# Master_Device.net
KiCad netlist of a schematic drawn in EAGLE
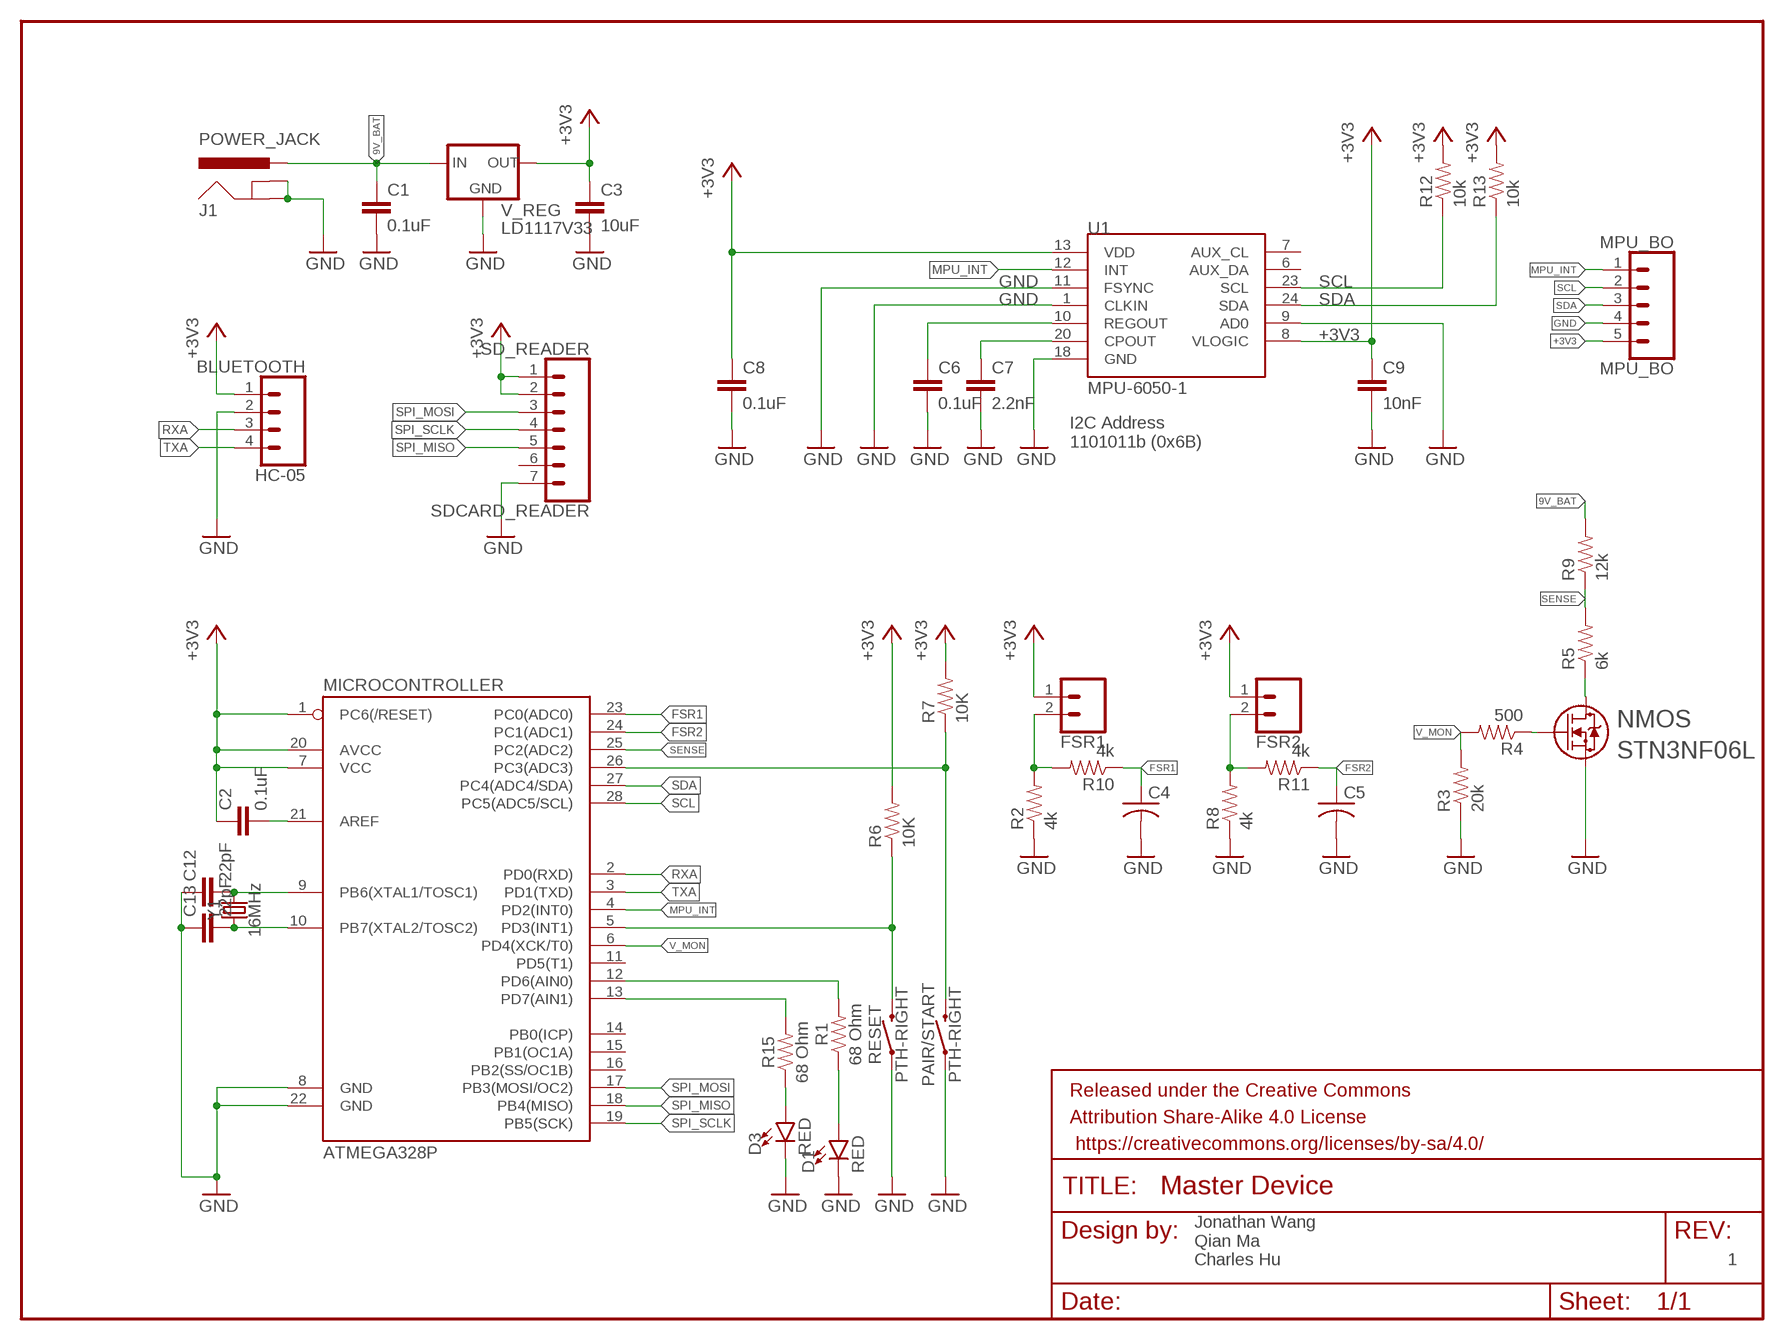
[diagram p0: schematic, sheet 1]

(export (version "E")
  (design (tool "Eeschema 10.0.6"))
  (components
    (comp (ref "C1")
      (value "0.1uF")
      (footprint "eagle-import:0603-CAP")
      (libsource (lib "eagle-import") (part "CAP0603-CAP"))
    )
    (comp (ref "C2")
      (value "0.1uF")
      (footprint "eagle-import:0603-CAP")
      (libsource (lib "eagle-import") (part "CAP0603-CAP"))
    )
    (comp (ref "C3")
      (value "10uF")
      (footprint "eagle-import:0603-CAP")
      (libsource (lib "eagle-import") (part "CAP0603-CAP"))
    )
    (comp (ref "C4")
      (value "C-US050-050X075")
      (footprint "eagle-import:C050-050X075")
      (libsource (lib "eagle-import") (part "C-US050-050X075"))
    )
    (comp (ref "C5")
      (value "C-US050-050X075")
      (footprint "eagle-import:C050-050X075")
      (libsource (lib "eagle-import") (part "C-US050-050X075"))
    )
    (comp (ref "C6")
      (value "0.1uF")
      (footprint "eagle-import:0603-CAP")
      (libsource (lib "eagle-import") (part "CAP0603-CAP"))
    )
    (comp (ref "C7")
      (value "2.2nF")
      (footprint "eagle-import:0603-CAP")
      (libsource (lib "eagle-import") (part "CAP0603-CAP"))
    )
    (comp (ref "C8")
      (value "0.1uF")
      (footprint "eagle-import:0603-CAP")
      (libsource (lib "eagle-import") (part "CAP0603-CAP"))
    )
    (comp (ref "C9")
      (value "10nF")
      (footprint "eagle-import:0603-CAP")
      (libsource (lib "eagle-import") (part "CAP0603-CAP"))
    )
    (comp (ref "C12")
      (value "22pF")
      (footprint "eagle-import:0603")
      (libsource (lib "eagle-import") (part "22PF-0603-50V-5%"))
    )
    (comp (ref "C13")
      (value "22pF")
      (footprint "eagle-import:0603")
      (libsource (lib "eagle-import") (part "22PF-0603-50V-5%"))
    )
    (comp (ref "D1")
      (value "RED")
      (footprint "eagle-import:LED_3MM")
      (libsource (lib "eagle-import") (part "LED3MM"))
    )
    (comp (ref "D3")
      (value "RED")
      (footprint "eagle-import:LED_3MM")
      (libsource (lib "eagle-import") (part "LED3MM"))
    )
    (comp (ref "FRAME1")
      (value "FRAME-LETTERNO_PACKAGE")
      (footprint "eagle-import:DUMMY")
      (fields (field (name "DESIGNER") "Nobody"))
      (libsource (lib "eagle-import") (part "FRAME-LETTERNO_PACKAGE"))
    )
    (comp (ref "FSR1")
      (value "CONN_02")
      (footprint "eagle-import:1X02")
      (libsource (lib "eagle-import") (part "CONN_02"))
    )
    (comp (ref "FSR2")
      (value "CONN_02")
      (footprint "eagle-import:1X02")
      (libsource (lib "eagle-import") (part "CONN_02"))
    )
    (comp (ref "HC-05")
      (value "BLUETOOTH")
      (footprint "eagle-import:1X04")
      (libsource (lib "eagle-import") (part "CONN_04"))
    )
    (comp (ref "J1")
      (value "POWER_JACK")
      (footprint "eagle-import:POWER_JACK_PTH")
      (libsource (lib "eagle-import") (part "POWER_JACK"))
    )
    (comp (ref "MICROCONTROLLER")
      (value "ATMEGA328P")
      (footprint "eagle-import:DIP28")
      (libsource (lib "eagle-import") (part "ATMEGA328P_PDIP"))
    )
    (comp (ref "MPU_BO")
      (value "MPU_BO")
      (footprint "eagle-import:1X05")
      (libsource (lib "eagle-import") (part "CONN_05"))
    )
    (comp (ref "NMOS")
      (value "STN3NF06L")
      (footprint "eagle-import:SOT-223")
      (libsource (lib "eagle-import") (part "STN3NF06L"))
    )
    (comp (ref "PAIR/START")
      (value "PTH-RIGHT")
      (footprint "eagle-import:TACTILE_SWITCH_PTH_RIGHT_ANGLE_KIT")
      (libsource (lib "eagle-import") (part "MOMENTARY-SWITCH-SPST-PTH-RIGHT-ANGLE-KIT"))
    )
    (comp (ref "R1")
      (value "68 Ohm")
      (footprint "eagle-import:0603")
      (libsource (lib "eagle-import") (part "68OHM-0603-1/10W-1%"))
    )
    (comp (ref "R2")
      (value "4k")
      (footprint "eagle-import:0603-RES")
      (libsource (lib "eagle-import") (part "10KOHM-1/10W-1%(0603)0603"))
    )
    (comp (ref "R3")
      (value "20k")
      (footprint "eagle-import:0603-RES")
      (libsource (lib "eagle-import") (part "10KOHM-1/10W-1%(0603)0603"))
    )
    (comp (ref "R4")
      (value "500")
      (footprint "eagle-import:0603-RES")
      (libsource (lib "eagle-import") (part "10KOHM-1/10W-1%(0603)0603"))
    )
    (comp (ref "R5")
      (value "6k")
      (footprint "eagle-import:0603-RES")
      (libsource (lib "eagle-import") (part "10KOHM-1/10W-1%(0603)0603"))
    )
    (comp (ref "R6")
      (value "10K")
      (footprint "eagle-import:0603-RES")
      (libsource (lib "eagle-import") (part "10KOHM-1/10W-1%(0603)0603"))
    )
    (comp (ref "R7")
      (value "10K")
      (footprint "eagle-import:0603-RES")
      (libsource (lib "eagle-import") (part "10KOHM-1/10W-1%(0603)0603"))
    )
    (comp (ref "R8")
      (value "4k")
      (footprint "eagle-import:0603-RES")
      (libsource (lib "eagle-import") (part "10KOHM-1/10W-1%(0603)0603"))
    )
    (comp (ref "R9")
      (value "12k")
      (footprint "eagle-import:0603-RES")
      (libsource (lib "eagle-import") (part "10KOHM-1/10W-1%(0603)0603"))
    )
    (comp (ref "R10")
      (value "4k")
      (footprint "eagle-import:0603-RES")
      (libsource (lib "eagle-import") (part "10KOHM-1/10W-1%(0603)0603"))
    )
    (comp (ref "R11")
      (value "4k")
      (footprint "eagle-import:0603-RES")
      (libsource (lib "eagle-import") (part "10KOHM-1/10W-1%(0603)0603"))
    )
    (comp (ref "R12")
      (value "10k")
      (footprint "eagle-import:0603-RES")
      (libsource (lib "eagle-import") (part "RESISTOR0603-RES"))
    )
    (comp (ref "R13")
      (value "10k")
      (footprint "eagle-import:0603-RES")
      (libsource (lib "eagle-import") (part "RESISTOR0603-RES"))
    )
    (comp (ref "R15")
      (value "68 Ohm")
      (footprint "eagle-import:0603")
      (libsource (lib "eagle-import") (part "68OHM-0603-1/10W-1%"))
    )
    (comp (ref "RESET")
      (value "PTH-RIGHT")
      (footprint "eagle-import:TACTILE_SWITCH_PTH_RIGHT_ANGLE_KIT")
      (libsource (lib "eagle-import") (part "MOMENTARY-SWITCH-SPST-PTH-RIGHT-ANGLE-KIT"))
    )
    (comp (ref "SDCARD_READER")
      (value "SD_READER")
      (footprint "eagle-import:1X07")
      (libsource (lib "eagle-import") (part "CONN_07"))
    )
    (comp (ref "U1")
      (value "MPU-6050-1")
      (footprint "eagle-import:QFN-24-4MM2")
      (libsource (lib "eagle-import") (part "MPU-6050-1"))
    )
    (comp (ref "V_REG")
      (value "LD1117V33")
      (footprint "eagle-import:78XXL")
      (libsource (lib "eagle-import") (part "V_REG_LD1117VXX"))
    )
    (comp (ref "Y1")
      (value "16MHz")
      (footprint "eagle-import:HC49US")
      (libsource (lib "eagle-import") (part "CRYSTAL-16MHZPTH-HC49US"))
    )
  )
  (nets
    (net (code "1") (name "+3V3") (class "Default")
      (node (ref "C2") (pin "1") (pinfunction "1_1") (pintype "passive"))
      (node (ref "C3") (pin "1") (pinfunction "1_1") (pintype "passive"))
      (node (ref "C8") (pin "1") (pinfunction "1_1") (pintype "passive"))
      (node (ref "C9") (pin "1") (pinfunction "1_1") (pintype "passive"))
      (node (ref "FSR1") (pin "1") (pinfunction "1_1") (pintype "passive"))
      (node (ref "FSR2") (pin "1") (pinfunction "1_1") (pintype "passive"))
      (node (ref "HC-05") (pin "1") (pinfunction "1_1") (pintype "passive"))
      (node (ref "MICROCONTROLLER") (pin "1") (pinfunction "PC6(/RESET)_1") (pintype "bidirectional"))
      (node (ref "MICROCONTROLLER") (pin "20") (pinfunction "AVCC_20") (pintype "bidirectional"))
      (node (ref "MICROCONTROLLER") (pin "7") (pinfunction "VCC_7") (pintype "bidirectional"))
      (node (ref "MPU_BO") (pin "5") (pinfunction "5_5") (pintype "passive"))
      (node (ref "R12") (pin "2") (pinfunction "2_2") (pintype "passive"))
      (node (ref "R13") (pin "2") (pinfunction "2_2") (pintype "passive"))
      (node (ref "R6") (pin "2") (pinfunction "2_2") (pintype "passive"))
      (node (ref "R7") (pin "2") (pinfunction "2_2") (pintype "passive"))
      (node (ref "SDCARD_READER") (pin "1") (pinfunction "1_1") (pintype "passive"))
      (node (ref "SDCARD_READER") (pin "2") (pinfunction "2_2") (pintype "passive"))
      (node (ref "U1") (pin "13") (pinfunction "VDD_13") (pintype "bidirectional"))
      (node (ref "U1") (pin "8") (pinfunction "VLOGIC_8") (pintype "bidirectional"))
      (node (ref "V_REG") (pin "GND") (pinfunction "OUT_GND") (pintype "passive"))
    )
    (net (code "2") (name "9V_BAT") (class "Default")
      (node (ref "C1") (pin "1") (pinfunction "1_1") (pintype "passive"))
      (node (ref "J1") (pin "PWR") (pinfunction "PWR_PWR") (pintype "bidirectional"))
      (node (ref "R9") (pin "2") (pinfunction "2_2") (pintype "passive"))
      (node (ref "V_REG") (pin "OUT") (pinfunction "IN_OUT") (pintype "input"))
    )
    (net (code "3") (name "FSR1") (class "Default")
      (node (ref "C4") (pin "1") (pinfunction "1_1") (pintype "passive"))
      (node (ref "MICROCONTROLLER") (pin "23") (pinfunction "PC0(ADC0)_23") (pintype "bidirectional"))
      (node (ref "R10") (pin "1") (pinfunction "1_1") (pintype "passive"))
    )
    (net (code "4") (name "FSR2") (class "Default")
      (node (ref "C5") (pin "1") (pinfunction "1_1") (pintype "passive"))
      (node (ref "MICROCONTROLLER") (pin "24") (pinfunction "PC1(ADC1)_24") (pintype "bidirectional"))
      (node (ref "R11") (pin "1") (pinfunction "1_1") (pintype "passive"))
    )
    (net (code "5") (name "GND") (class "Default")
      (node (ref "C1") (pin "2") (pinfunction "2_2") (pintype "passive"))
      (node (ref "C12") (pin "1") (pinfunction "1_1") (pintype "passive"))
      (node (ref "C13") (pin "1") (pinfunction "1_1") (pintype "passive"))
      (node (ref "C3") (pin "2") (pinfunction "2_2") (pintype "passive"))
      (node (ref "C4") (pin "2") (pinfunction "2_2") (pintype "passive"))
      (node (ref "C5") (pin "2") (pinfunction "2_2") (pintype "passive"))
      (node (ref "C6") (pin "2") (pinfunction "2_2") (pintype "passive"))
      (node (ref "C7") (pin "2") (pinfunction "2_2") (pintype "passive"))
      (node (ref "C8") (pin "2") (pinfunction "2_2") (pintype "passive"))
      (node (ref "C9") (pin "2") (pinfunction "2_2") (pintype "passive"))
      (node (ref "D1") (pin "K") (pinfunction "C_K") (pintype "passive"))
      (node (ref "D3") (pin "K") (pinfunction "C_K") (pintype "passive"))
      (node (ref "HC-05") (pin "2") (pinfunction "2_2") (pintype "passive"))
      (node (ref "J1") (pin "GND") (pinfunction "GND_GND") (pintype "bidirectional"))
      (node (ref "J1") (pin "GNDBREAK") (pinfunction "GNDBREAK_GNDBREAK") (pintype "bidirectional"))
      (node (ref "MICROCONTROLLER") (pin "22") (pinfunction "GND_22") (pintype "bidirectional"))
      (node (ref "MICROCONTROLLER") (pin "8") (pinfunction "GND_8") (pintype "bidirectional"))
      (node (ref "MPU_BO") (pin "4") (pinfunction "4_4") (pintype "passive"))
      (node (ref "NMOS") (pin "3") (pinfunction "3_3") (pintype "passive"))
      (node (ref "PAIR/START") (pin "1") (pinfunction "1_1") (pintype "passive"))
      (node (ref "R2") (pin "1") (pinfunction "1_1") (pintype "passive"))
      (node (ref "R3") (pin "1") (pinfunction "1_1") (pintype "passive"))
      (node (ref "R8") (pin "1") (pinfunction "1_1") (pintype "passive"))
      (node (ref "RESET") (pin "1") (pinfunction "1_1") (pintype "passive"))
      (node (ref "SDCARD_READER") (pin "7") (pinfunction "7_7") (pintype "passive"))
      (node (ref "U1") (pin "1") (pinfunction "CLKIN_1") (pintype "bidirectional"))
      (node (ref "U1") (pin "11") (pinfunction "FSYNC_11") (pintype "bidirectional"))
      (node (ref "U1") (pin "18") (pinfunction "GND_18") (pintype "bidirectional"))
      (node (ref "U1") (pin "9") (pinfunction "AD0_9") (pintype "bidirectional"))
      (node (ref "V_REG") (pin "IN") (pinfunction "GND_IN") (pintype "input"))
    )
    (net (code "6") (name "MPU_INT") (class "Default")
      (node (ref "MICROCONTROLLER") (pin "4") (pinfunction "PD2(INT0)_4") (pintype "bidirectional"))
      (node (ref "MPU_BO") (pin "1") (pinfunction "1_1") (pintype "passive"))
      (node (ref "U1") (pin "12") (pinfunction "INT_12") (pintype "bidirectional"))
    )
    (net (code "7") (name "Net-(D1-PadA)") (class "Default")
      (node (ref "D1") (pin "A") (pinfunction "A_A") (pintype "passive"))
      (node (ref "R1") (pin "1") (pinfunction "1_1") (pintype "passive"))
    )
    (net (code "8") (name "Net-(D3-PadA)") (class "Default")
      (node (ref "D3") (pin "A") (pinfunction "A_A") (pintype "passive"))
      (node (ref "R15") (pin "1") (pinfunction "1_1") (pintype "passive"))
    )
    (net (code "9") (name "Net-(FSR1-Pad2)") (class "Default")
      (node (ref "FSR1") (pin "2") (pinfunction "2_2") (pintype "passive"))
      (node (ref "R10") (pin "2") (pinfunction "2_2") (pintype "passive"))
      (node (ref "R2") (pin "2") (pinfunction "2_2") (pintype "passive"))
    )
    (net (code "10") (name "Net-(FSR2-Pad2)") (class "Default")
      (node (ref "FSR2") (pin "2") (pinfunction "2_2") (pintype "passive"))
      (node (ref "R11") (pin "2") (pinfunction "2_2") (pintype "passive"))
      (node (ref "R8") (pin "2") (pinfunction "2_2") (pintype "passive"))
    )
    (net (code "11") (name "Net-(MICROCONTROLLER-AREF)") (class "Default")
      (node (ref "C2") (pin "2") (pinfunction "2_2") (pintype "passive"))
      (node (ref "MICROCONTROLLER") (pin "21") (pinfunction "AREF_21") (pintype "bidirectional"))
    )
    (net (code "12") (name "Net-(MICROCONTROLLER-PB6(XTAL1{slash}TOSC1))") (class "Default")
      (node (ref "C12") (pin "2") (pinfunction "2_2") (pintype "passive"))
      (node (ref "MICROCONTROLLER") (pin "9") (pinfunction "PB6(XTAL1/TOSC1)_9") (pintype "bidirectional"))
      (node (ref "Y1") (pin "2") (pinfunction "2_2") (pintype "passive"))
    )
    (net (code "13") (name "Net-(MICROCONTROLLER-PB7(XTAL2{slash}TOSC2))") (class "Default")
      (node (ref "C13") (pin "2") (pinfunction "2_2") (pintype "passive"))
      (node (ref "MICROCONTROLLER") (pin "10") (pinfunction "PB7(XTAL2/TOSC2)_10") (pintype "bidirectional"))
      (node (ref "Y1") (pin "1") (pinfunction "1_1") (pintype "passive"))
    )
    (net (code "14") (name "Net-(MICROCONTROLLER-PC3(ADC3))") (class "Default")
      (node (ref "MICROCONTROLLER") (pin "26") (pinfunction "PC3(ADC3)_26") (pintype "bidirectional"))
      (node (ref "PAIR/START") (pin "2") (pinfunction "2_2") (pintype "passive"))
      (node (ref "R7") (pin "1") (pinfunction "1_1") (pintype "passive"))
    )
    (net (code "15") (name "Net-(MICROCONTROLLER-PD3(INT1))") (class "Default")
      (node (ref "MICROCONTROLLER") (pin "5") (pinfunction "PD3(INT1)_5") (pintype "bidirectional"))
      (node (ref "R6") (pin "1") (pinfunction "1_1") (pintype "passive"))
      (node (ref "RESET") (pin "2") (pinfunction "2_2") (pintype "passive"))
    )
    (net (code "16") (name "Net-(MICROCONTROLLER-PD6(AIN0))") (class "Default")
      (node (ref "MICROCONTROLLER") (pin "12") (pinfunction "PD6(AIN0)_12") (pintype "bidirectional"))
      (node (ref "R1") (pin "2") (pinfunction "2_2") (pintype "passive"))
    )
    (net (code "17") (name "Net-(MICROCONTROLLER-PD7(AIN1))") (class "Default")
      (node (ref "MICROCONTROLLER") (pin "13") (pinfunction "PD7(AIN1)_13") (pintype "bidirectional"))
      (node (ref "R15") (pin "2") (pinfunction "2_2") (pintype "passive"))
    )
    (net (code "18") (name "Net-(NMOS-Pad1)") (class "Default")
      (node (ref "NMOS") (pin "1") (pinfunction "1_1") (pintype "passive"))
      (node (ref "R4") (pin "1") (pinfunction "1_1") (pintype "passive"))
    )
    (net (code "19") (name "Net-(NMOS-Pad2)") (class "Default")
      (node (ref "NMOS") (pin "2") (pinfunction "2_2") (pintype "passive"))
      (node (ref "R5") (pin "1") (pinfunction "1_1") (pintype "passive"))
    )
    (net (code "20") (name "Net-(U1-CPOUT)") (class "Default")
      (node (ref "C7") (pin "1") (pinfunction "1_1") (pintype "passive"))
      (node (ref "U1") (pin "20") (pinfunction "CPOUT_20") (pintype "bidirectional"))
    )
    (net (code "21") (name "Net-(U1-REGOUT)") (class "Default")
      (node (ref "C6") (pin "1") (pinfunction "1_1") (pintype "passive"))
      (node (ref "U1") (pin "10") (pinfunction "REGOUT_10") (pintype "bidirectional"))
    )
    (net (code "22") (name "RXA") (class "Default")
      (node (ref "HC-05") (pin "3") (pinfunction "3_3") (pintype "passive"))
      (node (ref "MICROCONTROLLER") (pin "2") (pinfunction "PD0(RXD)_2") (pintype "bidirectional"))
    )
    (net (code "23") (name "SCL") (class "Default")
      (node (ref "MICROCONTROLLER") (pin "28") (pinfunction "PC5(ADC5/SCL)_28") (pintype "bidirectional"))
      (node (ref "MPU_BO") (pin "2") (pinfunction "2_2") (pintype "passive"))
      (node (ref "R12") (pin "1") (pinfunction "1_1") (pintype "passive"))
      (node (ref "U1") (pin "23") (pinfunction "SCL_23") (pintype "bidirectional"))
    )
    (net (code "24") (name "SDA") (class "Default")
      (node (ref "MICROCONTROLLER") (pin "27") (pinfunction "PC4(ADC4/SDA)_27") (pintype "bidirectional"))
      (node (ref "MPU_BO") (pin "3") (pinfunction "3_3") (pintype "passive"))
      (node (ref "R13") (pin "1") (pinfunction "1_1") (pintype "passive"))
      (node (ref "U1") (pin "24") (pinfunction "SDA_24") (pintype "bidirectional"))
    )
    (net (code "25") (name "SENSE") (class "Default")
      (node (ref "MICROCONTROLLER") (pin "25") (pinfunction "PC2(ADC2)_25") (pintype "bidirectional"))
      (node (ref "R5") (pin "2") (pinfunction "2_2") (pintype "passive"))
      (node (ref "R9") (pin "1") (pinfunction "1_1") (pintype "passive"))
    )
    (net (code "26") (name "SPI_MISO") (class "Default")
      (node (ref "MICROCONTROLLER") (pin "18") (pinfunction "PB4(MISO)_18") (pintype "bidirectional"))
      (node (ref "SDCARD_READER") (pin "5") (pinfunction "5_5") (pintype "passive"))
    )
    (net (code "27") (name "SPI_MOSI") (class "Default")
      (node (ref "MICROCONTROLLER") (pin "17") (pinfunction "PB3(MOSI/OC2)_17") (pintype "bidirectional"))
      (node (ref "SDCARD_READER") (pin "3") (pinfunction "3_3") (pintype "passive"))
    )
    (net (code "28") (name "SPI_SCLK") (class "Default")
      (node (ref "MICROCONTROLLER") (pin "19") (pinfunction "PB5(SCK)_19") (pintype "bidirectional"))
      (node (ref "SDCARD_READER") (pin "4") (pinfunction "4_4") (pintype "passive"))
    )
    (net (code "29") (name "TXA") (class "Default")
      (node (ref "HC-05") (pin "4") (pinfunction "4_4") (pintype "passive"))
      (node (ref "MICROCONTROLLER") (pin "3") (pinfunction "PD1(TXD)_3") (pintype "bidirectional"))
    )
    (net (code "30") (name "V_MON") (class "Default")
      (node (ref "MICROCONTROLLER") (pin "6") (pinfunction "PD4(XCK/T0)_6") (pintype "bidirectional"))
      (node (ref "R3") (pin "2") (pinfunction "2_2") (pintype "passive"))
      (node (ref "R4") (pin "2") (pinfunction "2_2") (pintype "passive"))
    )
    (net (code "31") (name "unconnected-(MICROCONTROLLER-PB0(ICP)-Pad14)") (class "Default")
      (node (ref "MICROCONTROLLER") (pin "14") (pinfunction "PB0(ICP)_14") (pintype "bidirectional"))
    )
    (net (code "32") (name "unconnected-(MICROCONTROLLER-PB1(OC1A)-Pad15)") (class "Default")
      (node (ref "MICROCONTROLLER") (pin "15") (pinfunction "PB1(OC1A)_15") (pintype "bidirectional"))
    )
    (net (code "33") (name "unconnected-(MICROCONTROLLER-PB2(SS{slash}OC1B)-Pad16)") (class "Default")
      (node (ref "MICROCONTROLLER") (pin "16") (pinfunction "PB2(SS/OC1B)_16") (pintype "bidirectional"))
    )
    (net (code "34") (name "unconnected-(MICROCONTROLLER-PD5(T1)-Pad11)") (class "Default")
      (node (ref "MICROCONTROLLER") (pin "11") (pinfunction "PD5(T1)_11") (pintype "bidirectional"))
    )
    (net (code "35") (name "unconnected-(SDCARD_READER-Pad6)") (class "Default")
      (node (ref "SDCARD_READER") (pin "6") (pinfunction "6_6") (pintype "passive"))
    )
    (net (code "36") (name "unconnected-(U1-AUX_CL-Pad7)") (class "Default")
      (node (ref "U1") (pin "7") (pinfunction "AUX_CL_7") (pintype "bidirectional"))
    )
    (net (code "37") (name "unconnected-(U1-AUX_DA-Pad6)") (class "Default")
      (node (ref "U1") (pin "6") (pinfunction "AUX_DA_6") (pintype "bidirectional"))
    )
  )
)
